# SP.net
KiCad netlist of a schematic drawn in EAGLE
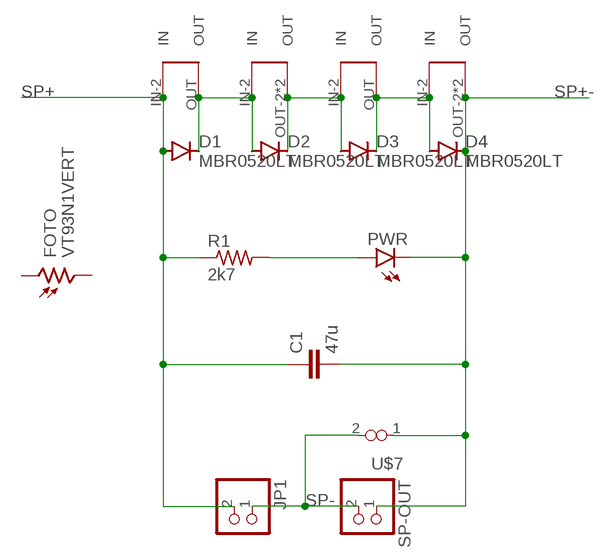
[diagram p0: schematic, sheet 1]

(export (version "E")
  (design (tool "Eeschema 10.0.6"))
  (components
    (comp (ref "C1")
      (value "47u")
      (footprint "eagle-import:C1210")
      (libsource (lib "eagle-import") (part "C-EUC1210"))
    )
    (comp (ref "D1")
      (value "MBR0520LT")
      (footprint "eagle-import:SOD123")
      (libsource (lib "eagle-import") (part "MBR0520LT"))
    )
    (comp (ref "D2")
      (value "MBR0520LT")
      (footprint "eagle-import:SOD123")
      (libsource (lib "eagle-import") (part "MBR0520LT"))
    )
    (comp (ref "D3")
      (value "MBR0520LT")
      (footprint "eagle-import:SOD123")
      (libsource (lib "eagle-import") (part "MBR0520LT"))
    )
    (comp (ref "D4")
      (value "MBR0520LT")
      (footprint "eagle-import:SOD123")
      (libsource (lib "eagle-import") (part "MBR0520LT"))
    )
    (comp (ref "FOTO")
      (value "VT93N1VERT")
      (footprint "eagle-import:VT93N1-VERT")
      (libsource (lib "eagle-import") (part "VT93N1VERT"))
    )
    (comp (ref "JP1")
      (value "PINHD-1X2")
      (footprint "eagle-import:1X02")
      (libsource (lib "eagle-import") (part "PINHD-1X2"))
    )
    (comp (ref "PWR")
      (value "LEDCHIP-LED0603")
      (footprint "eagle-import:CHIP-LED0603")
      (libsource (lib "eagle-import") (part "LEDCHIP-LED0603"))
    )
    (comp (ref "R1")
      (value "2k7")
      (footprint "eagle-import:R0603")
      (libsource (lib "eagle-import") (part "R-US_R0603"))
    )
    (comp (ref "SP-OUT")
      (value "PINHD-1X2")
      (footprint "eagle-import:1X02")
      (libsource (lib "eagle-import") (part "PINHD-1X2"))
    )
    (comp (ref "U$1")
      (value "SOLAR-2_1")
      (footprint "eagle-import:SOLAR_1-2")
      (libsource (lib "eagle-import") (part "SOLAR-2_1"))
    )
    (comp (ref "U$2")
      (value "SOLAR-2_0")
      (footprint "eagle-import:SOLAR_0-2")
      (libsource (lib "eagle-import") (part "SOLAR-2_0"))
    )
    (comp (ref "U$3")
      (value "SOLAR-2_1")
      (footprint "eagle-import:SOLAR_1-2")
      (libsource (lib "eagle-import") (part "SOLAR-2_1"))
    )
    (comp (ref "U$4")
      (value "SOLAR-2_0")
      (footprint "eagle-import:SOLAR_0-2")
      (libsource (lib "eagle-import") (part "SOLAR-2_0"))
    )
    (comp (ref "U$7")
      (value "VIAS-CONNECT")
      (footprint "eagle-import:VIAS-CONNECT")
      (libsource (lib "eagle-import") (part "VIAS-CONNECT"))
    )
  )
  (nets
    (net (code "1") (name "/SP+") (class "Default")
      (node (ref "C1") (pin "1") (pinfunction "1_1") (pintype "passive"))
      (node (ref "D1") (pin "A") (pinfunction "A_A") (pintype "passive"))
      (node (ref "JP1") (pin "2") (pinfunction "2_2") (pintype "passive"))
      (node (ref "R1") (pin "1") (pinfunction "1_1") (pintype "passive"))
      (node (ref "U$1") (pin "IN-2") (pinfunction "IN_IN-2") (pintype "bidirectional"))
    )
    (net (code "2") (name "/SP+-") (class "Default")
      (node (ref "C1") (pin "2") (pinfunction "2_2") (pintype "passive"))
      (node (ref "D4") (pin "C") (pinfunction "C_C") (pintype "passive"))
      (node (ref "PWR") (pin "C") (pinfunction "C_C") (pintype "passive"))
      (node (ref "SP-OUT") (pin "1") (pinfunction "1_1") (pintype "passive"))
      (node (ref "U$4") (pin "OUT-2") (pinfunction "OUT_OUT-2") (pintype "bidirectional"))
      (node (ref "U$4") (pin "OUT-21") (pinfunction "OUT_OUT-21") (pintype "bidirectional"))
      (node (ref "U$7") (pin "1") (pinfunction "1_1") (pintype "passive"))
    )
    (net (code "3") (name "/SP-") (class "Default")
      (node (ref "JP1") (pin "1") (pinfunction "1_1") (pintype "passive"))
      (node (ref "SP-OUT") (pin "2") (pinfunction "2_2") (pintype "passive"))
      (node (ref "U$7") (pin "2") (pinfunction "2_2") (pintype "passive"))
    )
    (net (code "4") (name "Net-(PWR-PadA)") (class "Default")
      (node (ref "PWR") (pin "A") (pinfunction "A_A") (pintype "passive"))
      (node (ref "R1") (pin "2") (pinfunction "2_2") (pintype "passive"))
    )
    (net (code "5") (name "Net-(U$2-IN)") (class "Default")
      (node (ref "D1") (pin "C") (pinfunction "C_C") (pintype "passive"))
      (node (ref "D2") (pin "A") (pinfunction "A_A") (pintype "passive"))
      (node (ref "U$1") (pin "OUT") (pinfunction "OUT_OUT") (pintype "bidirectional"))
      (node (ref "U$2") (pin "IN-2") (pinfunction "IN_IN-2") (pintype "bidirectional"))
    )
    (net (code "6") (name "Net-(U$3-IN)") (class "Default")
      (node (ref "D2") (pin "C") (pinfunction "C_C") (pintype "passive"))
      (node (ref "D3") (pin "A") (pinfunction "A_A") (pintype "passive"))
      (node (ref "U$2") (pin "OUT-2") (pinfunction "OUT_OUT-2") (pintype "bidirectional"))
      (node (ref "U$2") (pin "OUT-21") (pinfunction "OUT_OUT-21") (pintype "bidirectional"))
      (node (ref "U$3") (pin "IN-2") (pinfunction "IN_IN-2") (pintype "bidirectional"))
    )
    (net (code "7") (name "Net-(U$4-IN)") (class "Default")
      (node (ref "D3") (pin "C") (pinfunction "C_C") (pintype "passive"))
      (node (ref "D4") (pin "A") (pinfunction "A_A") (pintype "passive"))
      (node (ref "U$3") (pin "OUT") (pinfunction "OUT_OUT") (pintype "bidirectional"))
      (node (ref "U$4") (pin "IN-2") (pinfunction "IN_IN-2") (pintype "bidirectional"))
    )
    (net (code "8") (name "unconnected-(FOTO-1-PadP$1)") (class "Default")
      (node (ref "FOTO") (pin "P$1") (pinfunction "1_P$1") (pintype "passive"))
    )
    (net (code "9") (name "unconnected-(FOTO-2-PadP$2)") (class "Default")
      (node (ref "FOTO") (pin "P$2") (pinfunction "2_P$2") (pintype "passive"))
    )
  )
)
